# Upconversion.net
KiCad netlist of a schematic drawn in Altium Designer
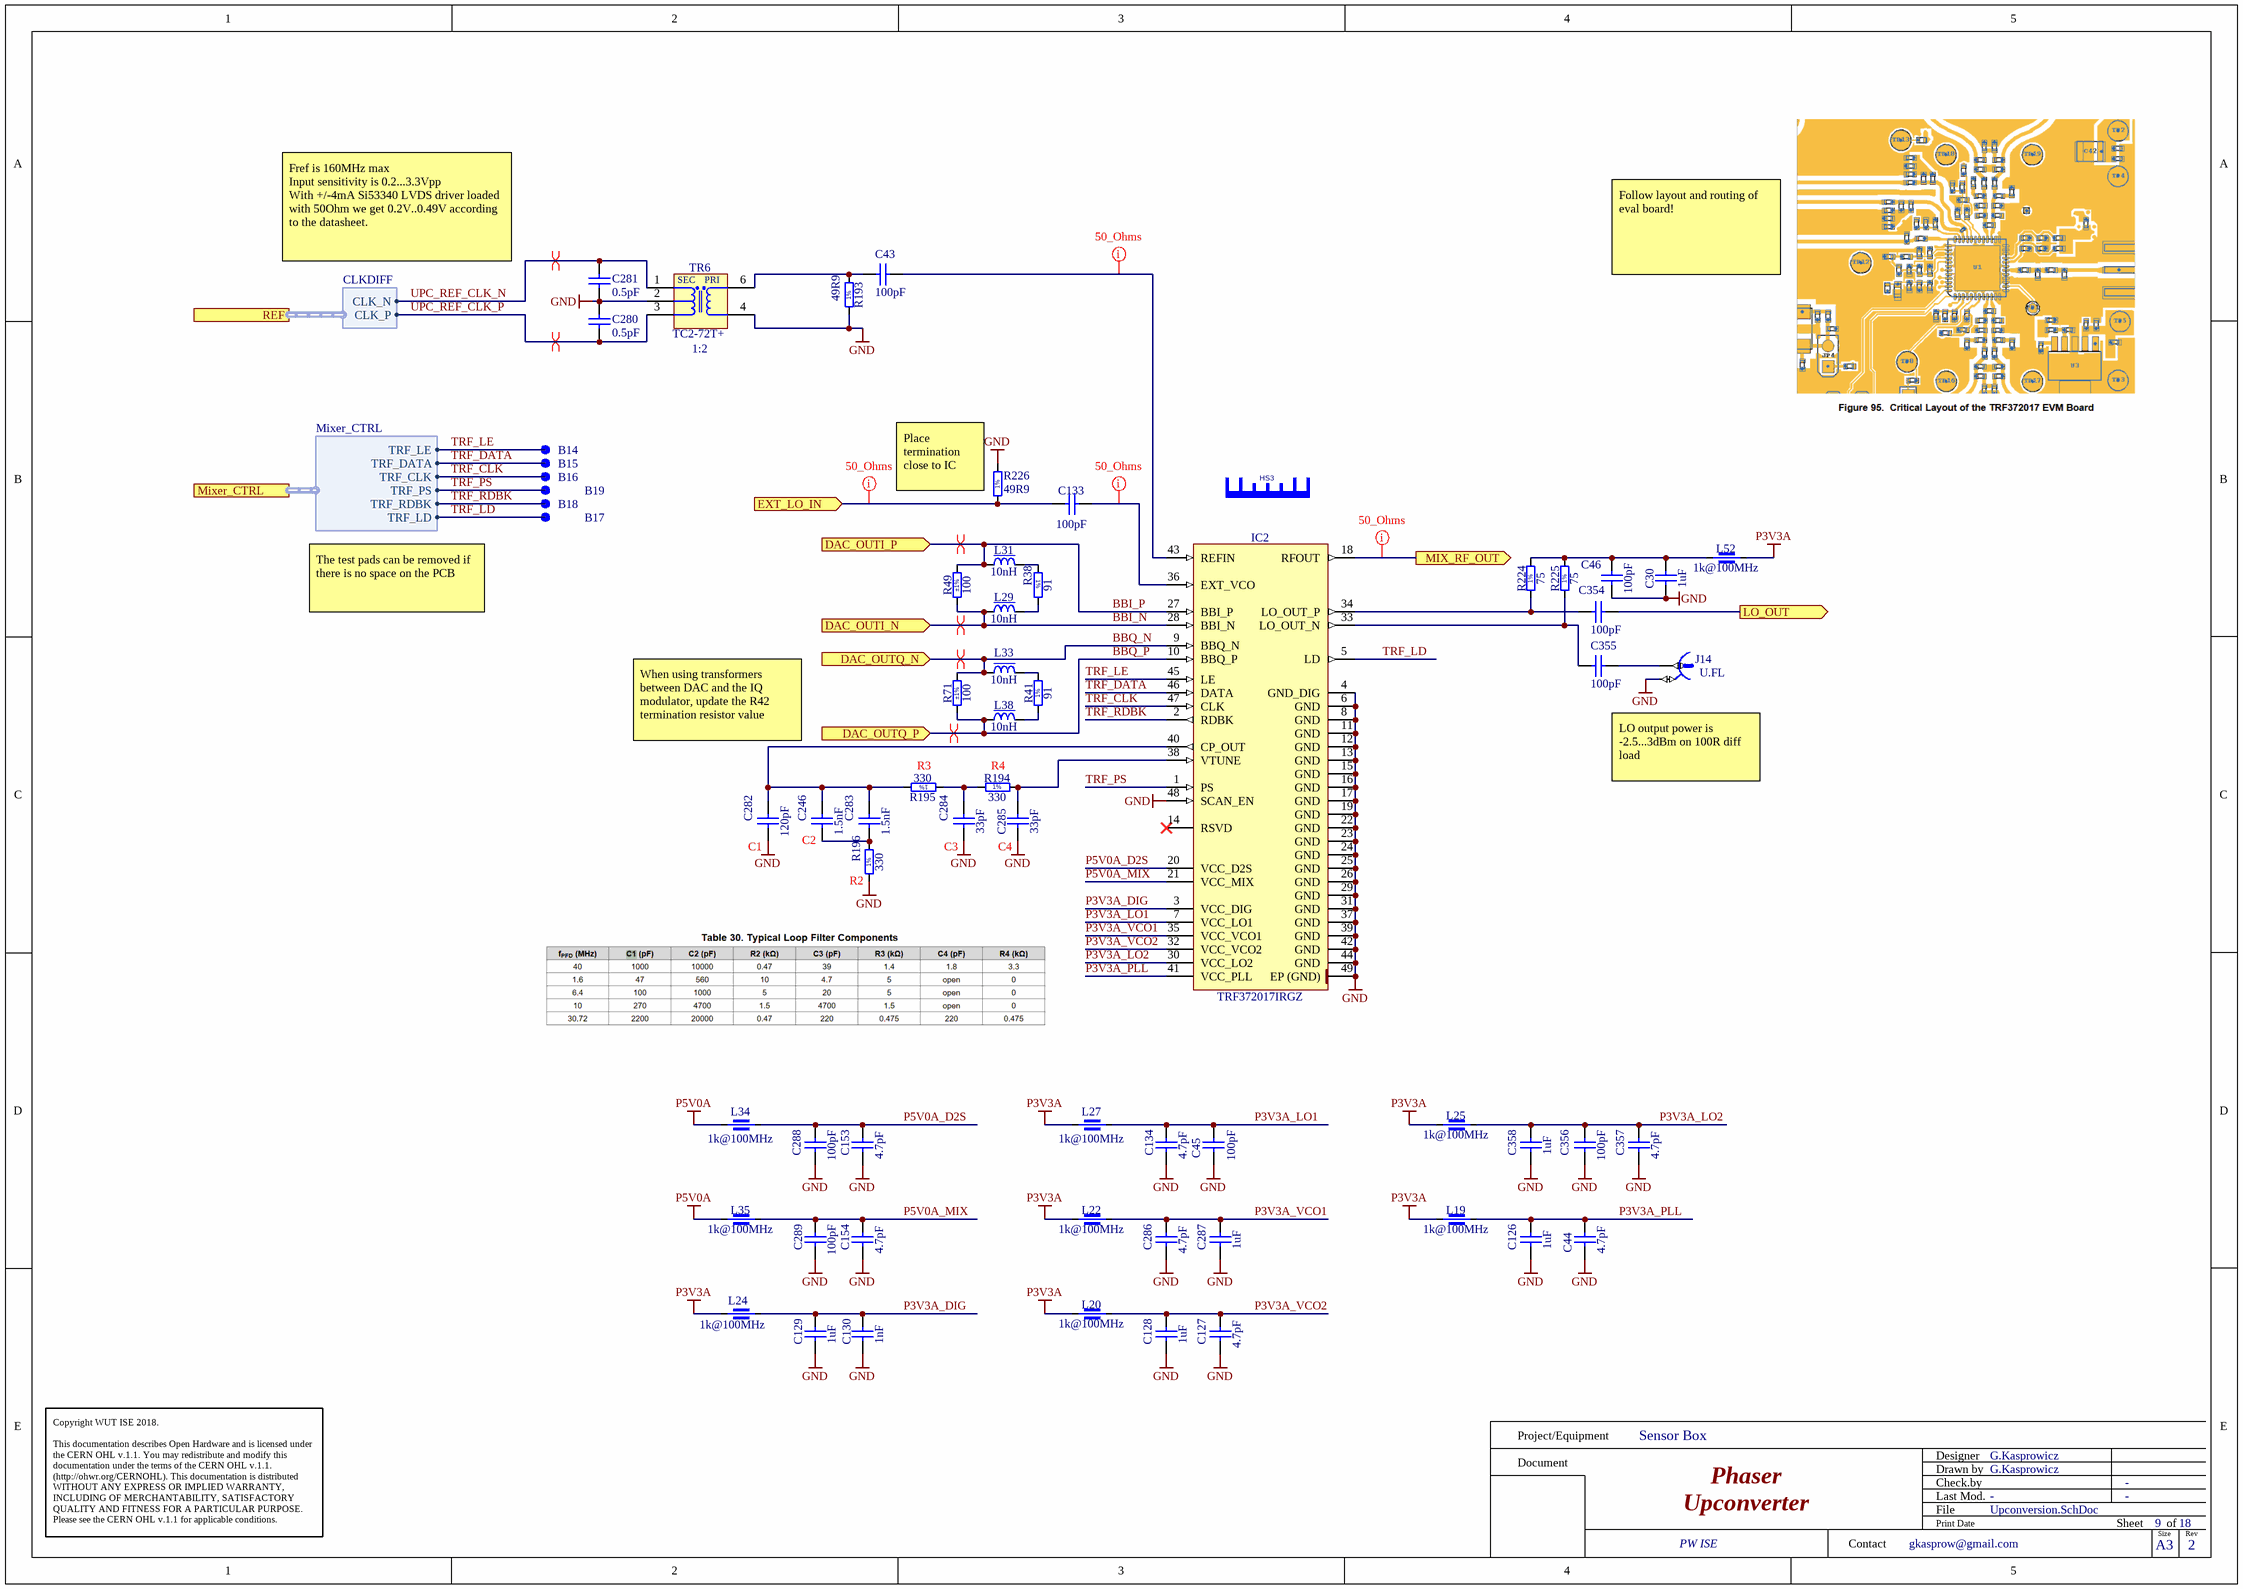
[diagram p0: Upconversion.SchDoc]

(export (version "E")
  (design (tool "Eeschema 10.0.6"))
  (components
    (comp (ref "B14")
      (value "SMD Pad")
      (footprint "C100")
      (description "Through Hole Pad")
      (fields (field (name "PART NUMBER") "SMD_PAD_D1MM") (field (name "AUTHOR") "CERN DEM JLC"))
      (libsource (lib "Eletro-mechanical") (part "Single SMD Pad (Round)"))
    )
    (comp (ref "B15")
      (value "SMD Pad")
      (footprint "C100")
      (description "Through Hole Pad")
      (fields (field (name "PART NUMBER") "SMD_PAD_D1MM") (field (name "AUTHOR") "CERN DEM JLC"))
      (libsource (lib "Eletro-mechanical") (part "Single SMD Pad (Round)"))
    )
    (comp (ref "B16")
      (value "SMD Pad")
      (footprint "C100")
      (description "Through Hole Pad")
      (fields (field (name "PART NUMBER") "SMD_PAD_D1MM") (field (name "AUTHOR") "CERN DEM JLC"))
      (libsource (lib "Eletro-mechanical") (part "Single SMD Pad (Round)"))
    )
    (comp (ref "B17")
      (value "SMD Pad")
      (footprint "C100")
      (description "Through Hole Pad")
      (fields (field (name "PART NUMBER") "SMD_PAD_D1MM") (field (name "AUTHOR") "CERN DEM JLC"))
      (libsource (lib "Eletro-mechanical") (part "Single SMD Pad (Round)"))
    )
    (comp (ref "B18")
      (value "SMD Pad")
      (footprint "C100")
      (description "Through Hole Pad")
      (fields (field (name "PART NUMBER") "SMD_PAD_D1MM") (field (name "AUTHOR") "CERN DEM JLC"))
      (libsource (lib "Eletro-mechanical") (part "Single SMD Pad (Round)"))
    )
    (comp (ref "B19")
      (value "SMD Pad")
      (footprint "C100")
      (description "Through Hole Pad")
      (fields (field (name "PART NUMBER") "SMD_PAD_D1MM") (field (name "AUTHOR") "CERN DEM JLC"))
      (libsource (lib "Eletro-mechanical") (part "Single SMD Pad (Round)"))
    )
    (comp (ref "C30")
      (value "1uF")
      (footprint "CAPC1005X55N")
      (description "Non-polarised capacitor")
      (fields
        (field (name "PART NUMBER") "CC0402_1UF_16V_10%_X5R")
        (field (name "VOLTAGE") "16V")
        (field (name "AUTHOR") "CERN DEM JLC")
      )
      (libsource (lib "Capacitors") (part "Capacitor - non polarized"))
    )
    (comp (ref "C43")
      (value "100pF")
      (footprint "CAPC1005X55N")
      (description "Non-polarised capacitor")
      (fields
        (field (name "PART NUMBER") "CC0402_100PF_50V_5%_C0G")
        (field (name "VOLTAGE") "50V")
        (field (name "AUTHOR") "CERN DEM JLC")
      )
      (libsource (lib "Capacitors") (part "Capacitor - non polarized"))
    )
    (comp (ref "C44")
      (value "4.7pF")
      (footprint "CAPC1005X55N")
      (description "Non-polarised capacitor")
      (fields
        (field (name "PART NUMBER") "CC0402_4.7PF_50V_0.25PF_C0G")
        (field (name "VOLTAGE") "50V")
        (field (name "AUTHOR") "CERN DEM JLC")
      )
      (libsource (lib "Capacitors") (part "Capacitor - non polarized"))
    )
    (comp (ref "C45")
      (value "100pF")
      (footprint "CAPC1005X55N")
      (description "Non-polarised capacitor")
      (fields
        (field (name "PART NUMBER") "CC0402_100PF_50V_5%_C0G")
        (field (name "VOLTAGE") "50V")
        (field (name "AUTHOR") "CERN DEM JLC")
      )
      (libsource (lib "Capacitors") (part "Capacitor - non polarized"))
    )
    (comp (ref "C46")
      (value "100pF")
      (footprint "CAPC1005X55N")
      (description "Non-polarised capacitor")
      (fields
        (field (name "PART NUMBER") "CC0402_100PF_50V_5%_C0G")
        (field (name "VOLTAGE") "50V")
        (field (name "AUTHOR") "CERN DEM JLC")
      )
      (libsource (lib "Capacitors") (part "Capacitor - non polarized"))
    )
    (comp (ref "C126")
      (value "1uF")
      (footprint "CAPC1005X55N")
      (description "Non-polarised capacitor")
      (fields
        (field (name "PART NUMBER") "CC0402_1UF_16V_10%_X5R")
        (field (name "VOLTAGE") "16V")
        (field (name "AUTHOR") "CERN DEM JLC")
      )
      (libsource (lib "Capacitors") (part "Capacitor - non polarized"))
    )
    (comp (ref "C127")
      (value "4.7pF")
      (footprint "CAPC1005X55N")
      (description "Non-polarised capacitor")
      (fields
        (field (name "PART NUMBER") "CC0402_4.7PF_50V_0.25PF_C0G")
        (field (name "VOLTAGE") "50V")
        (field (name "AUTHOR") "CERN DEM JLC")
      )
      (libsource (lib "Capacitors") (part "Capacitor - non polarized"))
    )
    (comp (ref "C128")
      (value "1uF")
      (footprint "CAPC1005X55N")
      (description "Non-polarised capacitor")
      (fields
        (field (name "PART NUMBER") "CC0402_1UF_16V_10%_X5R")
        (field (name "VOLTAGE") "16V")
        (field (name "AUTHOR") "CERN DEM JLC")
      )
      (libsource (lib "Capacitors") (part "Capacitor - non polarized"))
    )
    (comp (ref "C129")
      (value "1uF")
      (footprint "CAPC1005X55N")
      (description "Non-polarised capacitor")
      (fields
        (field (name "PART NUMBER") "CC0402_1UF_16V_10%_X5R")
        (field (name "VOLTAGE") "16V")
        (field (name "AUTHOR") "CERN DEM JLC")
      )
      (libsource (lib "Capacitors") (part "Capacitor - non polarized"))
    )
    (comp (ref "C130")
      (value "1nF")
      (footprint "CAPC1005X55N")
      (description "Non-polarised capacitor")
      (fields
        (field (name "PART NUMBER") "CC0402_1NF_50V_10%_X7R")
        (field (name "VOLTAGE") "50V")
        (field (name "AUTHOR") "CERN DEM JLC")
      )
      (libsource (lib "Capacitors") (part "Capacitor - non polarized"))
    )
    (comp (ref "C133")
      (value "100pF")
      (footprint "CAPC1005X55N")
      (description "Non-polarised capacitor")
      (fields
        (field (name "PART NUMBER") "CC0402_100PF_50V_5%_C0G")
        (field (name "VOLTAGE") "50V")
        (field (name "AUTHOR") "CERN DEM JLC")
      )
      (libsource (lib "Capacitors") (part "Capacitor - non polarized"))
    )
    (comp (ref "C134")
      (value "4.7pF")
      (footprint "CAPC1005X55N")
      (description "Non-polarised capacitor")
      (fields
        (field (name "PART NUMBER") "CC0402_4.7PF_50V_0.25PF_C0G")
        (field (name "VOLTAGE") "50V")
        (field (name "AUTHOR") "CERN DEM JLC")
      )
      (libsource (lib "Capacitors") (part "Capacitor - non polarized"))
    )
    (comp (ref "C153")
      (value "4.7pF")
      (footprint "CAPC1005X55N")
      (description "Non-polarised capacitor")
      (fields
        (field (name "PART NUMBER") "CC0402_4.7PF_50V_0.25PF_C0G")
        (field (name "VOLTAGE") "50V")
        (field (name "AUTHOR") "CERN DEM JLC")
      )
      (libsource (lib "Capacitors") (part "Capacitor - non polarized"))
    )
    (comp (ref "C154")
      (value "4.7pF")
      (footprint "CAPC1005X55N")
      (description "Non-polarised capacitor")
      (fields
        (field (name "PART NUMBER") "CC0402_4.7PF_50V_0.25PF_C0G")
        (field (name "VOLTAGE") "50V")
        (field (name "AUTHOR") "CERN DEM JLC")
      )
      (libsource (lib "Capacitors") (part "Capacitor - non polarized"))
    )
    (comp (ref "C246")
      (value "1.5nF")
      (footprint "CAPC1608X87N")
      (description "Non-polarised capacitor")
      (fields
        (field (name "PART NUMBER") "CC0603_1.5NF_50V_5%_NP0")
        (field (name "VOLTAGE") "50V")
        (field (name "AUTHOR") "CERN DEM JLC")
      )
      (libsource (lib "Capacitors") (part "Capacitor - non polarized"))
    )
    (comp (ref "C280")
      (value "0.5pF")
      (footprint "CAPC1005X50N")
      (description "Non-polarised capacitor")
      (fields
        (field (name "PART NUMBER") "CC0402_0.5PF_25V_0.05PF_AVX_04023J0R5ABSTR")
        (field (name "VOLTAGE") "25V")
        (field (name "AUTHOR") "CERN DEM JLC")
      )
      (libsource (lib "Capacitors") (part "Capacitor - non polarized"))
    )
    (comp (ref "C281")
      (value "0.5pF")
      (footprint "CAPC1005X50N")
      (description "Non-polarised capacitor")
      (fields
        (field (name "PART NUMBER") "CC0402_0.5PF_25V_0.05PF_AVX_04023J0R5ABSTR")
        (field (name "VOLTAGE") "25V")
        (field (name "AUTHOR") "CERN DEM JLC")
      )
      (libsource (lib "Capacitors") (part "Capacitor - non polarized"))
    )
    (comp (ref "C282")
      (value "120pF")
      (footprint "CAPC1608X87N")
      (description "Non-polarised capacitor")
      (fields
        (field (name "PART NUMBER") "CC0603_120PF_50V_5%_NP0")
        (field (name "VOLTAGE") "50V")
        (field (name "AUTHOR") "CERN DEM JLC")
      )
      (libsource (lib "Capacitors") (part "Capacitor - non polarized"))
    )
    (comp (ref "C283")
      (value "1.5nF")
      (footprint "CAPC1608X87N")
      (description "Non-polarised capacitor")
      (fields
        (field (name "PART NUMBER") "CC0603_1.5NF_50V_5%_NP0")
        (field (name "VOLTAGE") "50V")
        (field (name "AUTHOR") "CERN DEM JLC")
      )
      (libsource (lib "Capacitors") (part "Capacitor - non polarized"))
    )
    (comp (ref "C284")
      (value "33pF")
      (footprint "CAPC2012X135N")
      (description "Non-polarised capacitor")
      (fields
        (field (name "PART NUMBER") "CC0805_33PF_50V_5%_NP0")
        (field (name "VOLTAGE") "50V")
        (field (name "AUTHOR") "CERN DEM JLC")
      )
      (libsource (lib "Capacitors") (part "Capacitor - non polarized"))
    )
    (comp (ref "C285")
      (value "33pF")
      (footprint "CAPC2012X135N")
      (description "Non-polarised capacitor")
      (fields
        (field (name "PART NUMBER") "CC0805_33PF_50V_5%_NP0")
        (field (name "MANUFACTURER") "GENERIC")
        (field (name "AUTHOR") "CERN DEM JLC")
      )
      (libsource (lib "Capacitors") (part "Capacitor - non polarized"))
    )
    (comp (ref "C286")
      (value "4.7pF")
      (footprint "CAPC1005X55N")
      (description "Non-polarised capacitor")
      (fields
        (field (name "PART NUMBER") "CC0402_4.7PF_50V_0.25PF_C0G")
        (field (name "VOLTAGE") "50V")
        (field (name "AUTHOR") "CERN DEM JLC")
      )
      (libsource (lib "Capacitors") (part "Capacitor - non polarized"))
    )
    (comp (ref "C287")
      (value "1uF")
      (footprint "CAPC1005X55N")
      (description "Non-polarised capacitor")
      (fields
        (field (name "PART NUMBER") "CC0402_1UF_16V_10%_X5R")
        (field (name "VOLTAGE") "16V")
        (field (name "AUTHOR") "CERN DEM JLC")
      )
      (libsource (lib "Capacitors") (part "Capacitor - non polarized"))
    )
    (comp (ref "C288")
      (value "100pF")
      (footprint "CAPC1005X55N")
      (description "Non-polarised capacitor")
      (fields
        (field (name "PART NUMBER") "CC0402_100PF_50V_5%_C0G")
        (field (name "VOLTAGE") "50V")
        (field (name "AUTHOR") "CERN DEM JLC")
      )
      (libsource (lib "Capacitors") (part "Capacitor - non polarized"))
    )
    (comp (ref "C289")
      (value "100pF")
      (footprint "CAPC1005X55N")
      (description "Non-polarised capacitor")
      (fields
        (field (name "PART NUMBER") "CC0402_100PF_50V_5%_C0G")
        (field (name "VOLTAGE") "50V")
        (field (name "AUTHOR") "CERN DEM JLC")
      )
      (libsource (lib "Capacitors") (part "Capacitor - non polarized"))
    )
    (comp (ref "C354")
      (value "100pF")
      (footprint "CAPC1005X55N")
      (description "Non-polarised capacitor")
      (fields
        (field (name "PART NUMBER") "CC0402_100PF_50V_5%_C0G")
        (field (name "VOLTAGE") "50V")
        (field (name "AUTHOR") "CERN DEM JLC")
      )
      (libsource (lib "Capacitors") (part "Capacitor - non polarized"))
    )
    (comp (ref "C355")
      (value "100pF")
      (footprint "CAPC1005X55N")
      (description "Non-polarised capacitor")
      (fields
        (field (name "PART NUMBER") "CC0402_100PF_50V_5%_C0G")
        (field (name "VOLTAGE") "50V")
        (field (name "AUTHOR") "CERN DEM JLC")
      )
      (libsource (lib "Capacitors") (part "Capacitor - non polarized"))
    )
    (comp (ref "C356")
      (value "100pF")
      (footprint "CAPC1005X55N")
      (description "Non-polarised capacitor")
      (fields
        (field (name "PART NUMBER") "CC0402_100PF_50V_5%_C0G")
        (field (name "VOLTAGE") "50V")
        (field (name "AUTHOR") "CERN DEM JLC")
      )
      (libsource (lib "Capacitors") (part "Capacitor - non polarized"))
    )
    (comp (ref "C357")
      (value "4.7pF")
      (footprint "CAPC1005X55N")
      (description "Non-polarised capacitor")
      (fields
        (field (name "PART NUMBER") "CC0402_4.7PF_50V_0.25PF_C0G")
        (field (name "VOLTAGE") "50V")
        (field (name "AUTHOR") "CERN DEM JLC")
      )
      (libsource (lib "Capacitors") (part "Capacitor - non polarized"))
    )
    (comp (ref "C358")
      (value "1uF")
      (footprint "CAPC1005X55N")
      (description "Non-polarised capacitor")
      (fields
        (field (name "PART NUMBER") "CC0402_1UF_16V_10%_X5R")
        (field (name "VOLTAGE") "16V")
        (field (name "AUTHOR") "CERN DEM JLC")
      )
      (libsource (lib "Capacitors") (part "Capacitor - non polarized"))
    )
    (comp (ref "HS3")
      (value "Heat Sink No Pad")
      (footprint "HSINK_17156")
      (description "Alphacool GPU RAM Aluminium Heatsinks 7x7mm - black")
      (fields
        (field (name "PART NUMBER") "4250197171564")
        (field (name "MANUFACTURER") "Alphacool")
        (field (name "AUTHOR") "GK")
      )
      (libsource (lib "Mechanical") (part "HEAT_SINK_IC_7x7x15"))
    )
    (comp (ref "IC2")
      (value "TRF372017IRGZ")
      (footprint "QFN50P700X700X100-49N-S560")
      (description "Integrated IQ Modulator PLL/VCO")
      (fields (field (name "MANUFACTURER") "TEXAS INSTRUMENTS") (field (name "AUTHOR") "CERN DEM JMW"))
      (libsource (lib "ICs And Semiconductors") (part "TRF372017"))
    )
    (comp (ref "J14")
      (value "U.FL")
      (footprint "HIROSE_U.FL-R-SMT-1(10)")
      (fields
        (field (name "MANUFACTURER") "HIROSE (HRS)")
        (field (name "MANUFACTURER PART NUMBER") "U.FL-R-SMT-1(10)")
        (field (name "PART NUMBER") "HIROSE_U.FL-R-SMT-1(10)")
        (field (name "AUTHOR") "CERN DEM JLC")
      )
      (libsource (lib "Connectors") (part "Coax_1Male_1Shield"))
    )
    (comp (ref "L19")
      (value "1k@100MHz")
      (footprint "INDC1005X55N")
      (fields
        (field (name "PART NUMBER") "IND0402_MURATA_BLM15HD102SN1")
        (field (name "POWER") "250mA")
        (field (name "TOLERANCE") "±25%")
        (field (name "AUTHOR") "CERN DEM JLC")
      )
      (libsource (lib "Inductors & Transformers") (part "Ferrite Bead"))
    )
    (comp (ref "L20")
      (value "1k@100MHz")
      (footprint "INDC1005X55N")
      (fields
        (field (name "PART NUMBER") "IND0402_MURATA_BLM15HD102SN1")
        (field (name "POWER") "250mA")
        (field (name "TOLERANCE") "±25%")
        (field (name "AUTHOR") "CERN DEM JLC")
      )
      (libsource (lib "Inductors & Transformers") (part "Ferrite Bead"))
    )
    (comp (ref "L22")
      (value "1k@100MHz")
      (footprint "INDC1005X55N")
      (fields
        (field (name "PART NUMBER") "IND0402_MURATA_BLM15HD102SN1")
        (field (name "POWER") "250mA")
        (field (name "TOLERANCE") "±25%")
        (field (name "AUTHOR") "CERN DEM JLC")
      )
      (libsource (lib "Inductors & Transformers") (part "Ferrite Bead"))
    )
    (comp (ref "L24")
      (value "1k@100MHz")
      (footprint "INDC1005X55N")
      (fields
        (field (name "PART NUMBER") "IND0402_MURATA_BLM15HD102SN1")
        (field (name "POWER") "250mA")
        (field (name "TOLERANCE") "±25%")
        (field (name "AUTHOR") "CERN DEM JLC")
      )
      (libsource (lib "") (part "Ferrite Bead_1"))
    )
    (comp (ref "L25")
      (value "1k@100MHz")
      (footprint "INDC1005X55N")
      (fields
        (field (name "PART NUMBER") "IND0402_MURATA_BLM15HD102SN1")
        (field (name "POWER") "250mA")
        (field (name "TOLERANCE") "±25%")
        (field (name "AUTHOR") "CERN DEM JLC")
      )
      (libsource (lib "Inductors & Transformers") (part "Ferrite Bead"))
    )
    (comp (ref "L27")
      (value "1k@100MHz")
      (footprint "INDC1005X55N")
      (fields
        (field (name "PART NUMBER") "IND0402_MURATA_BLM15HD102SN1")
        (field (name "POWER") "250mA")
        (field (name "TOLERANCE") "±25%")
        (field (name "AUTHOR") "CERN DEM JLC")
      )
      (libsource (lib "") (part "Ferrite Bead_2"))
    )
    (comp (ref "L29")
      (value "10nH")
      (footprint "IND_COILCRAFT_0402DC")
      (description "Inductor With Core")
      (fields
        (field (name "PART NUMBER") "IND0402_10NH_2%_COILCRAFT_0402DC")
        (field (name "POWER") "1A")
        (field (name "AUTHOR") "GK")
      )
      (libsource (lib "Inductors_Transformers") (part "IND0402_10NH_2%_COILCRAFT_0402DC"))
    )
    (comp (ref "L31")
      (value "10nH")
      (footprint "IND_COILCRAFT_0402DC")
      (description "Inductor With Core")
      (fields
        (field (name "PART NUMBER") "IND0402_10NH_2%_COILCRAFT_0402DC")
        (field (name "POWER") "1A")
        (field (name "AUTHOR") "GK")
      )
      (libsource (lib "Inductors_Transformers") (part "IND0402_10NH_2%_COILCRAFT_0402DC"))
    )
    (comp (ref "L33")
      (value "10nH")
      (footprint "IND_COILCRAFT_0402DC")
      (description "Inductor With Core")
      (fields
        (field (name "PART NUMBER") "IND0402_10NH_2%_COILCRAFT_0402DC")
        (field (name "POWER") "1A")
        (field (name "AUTHOR") "GK")
      )
      (libsource (lib "Inductors_Transformers") (part "IND0402_10NH_2%_COILCRAFT_0402DC"))
    )
    (comp (ref "L34")
      (value "1k@100MHz")
      (footprint "INDC1005X55N")
      (fields
        (field (name "PART NUMBER") "IND0402_MURATA_BLM15HD102SN1")
        (field (name "POWER") "250mA")
        (field (name "TOLERANCE") "±25%")
        (field (name "AUTHOR") "CERN DEM JLC")
      )
      (libsource (lib "") (part "Ferrite Bead_2"))
    )
    (comp (ref "L35")
      (value "1k@100MHz")
      (footprint "INDC1005X55N")
      (fields
        (field (name "PART NUMBER") "IND0402_MURATA_BLM15HD102SN1")
        (field (name "POWER") "250mA")
        (field (name "TOLERANCE") "±25%")
        (field (name "AUTHOR") "CERN DEM JLC")
      )
      (libsource (lib "Inductors & Transformers") (part "Ferrite Bead"))
    )
    (comp (ref "L38")
      (value "10nH")
      (footprint "IND_COILCRAFT_0402DC")
      (description "Inductor With Core")
      (fields
        (field (name "PART NUMBER") "IND0402_10NH_2%_COILCRAFT_0402DC")
        (field (name "POWER") "1A")
        (field (name "AUTHOR") "GK")
      )
      (libsource (lib "Inductors_Transformers") (part "IND0402_10NH_2%_COILCRAFT_0402DC"))
    )
    (comp (ref "L52")
      (value "1k@100MHz")
      (footprint "INDC1005X55N")
      (fields
        (field (name "PART NUMBER") "IND0402_MURATA_BLM15HD102SN1")
        (field (name "POWER") "250mA")
        (field (name "TOLERANCE") "±25%")
        (field (name "AUTHOR") "CERN DEM JLC")
      )
      (libsource (lib "") (part "Ferrite Bead_2"))
    )
    (comp (ref "R38")
      (value "91")
      (footprint "RESC1005X40N")
      (description "Resistor - 1%")
      (fields
        (field (name "PART NUMBER") "R0402_91R_1%_0.0625W_100PPM")
        (field (name "POWER") "0.0625W")
        (field (name "AUTHOR") "CERN DEM JLC")
      )
      (libsource (lib "Resistors") (part "Resistor - 1%"))
    )
    (comp (ref "R41")
      (value "91")
      (footprint "RESC1005X40N")
      (description "Resistor - 1%")
      (fields
        (field (name "PART NUMBER") "R0402_91R_1%_0.0625W_100PPM")
        (field (name "POWER") "0.0625W")
        (field (name "AUTHOR") "CERN DEM JLC")
      )
      (libsource (lib "Resistors") (part "Resistor - 1%"))
    )
    (comp (ref "R49")
      (value "100")
      (footprint "RESC1005X40N")
      (description "Resistor - 1%")
      (fields
        (field (name "TOLERANCE") "±1%")
        (field (name "PART NUMBER") "R0402_100R_1%_0.0625W_100PPM")
        (field (name "POWER") "0.0625W")
        (field (name "AUTHOR") "CERN DEM JLC")
      )
      (libsource (lib "") (part "Resistor - 1%_1"))
    )
    (comp (ref "R71")
      (value "100")
      (footprint "RESC1005X40N")
      (description "Resistor - 1%")
      (fields
        (field (name "TOLERANCE") "±1%")
        (field (name "PART NUMBER") "R0402_100R_1%_0.0625W_100PPM")
        (field (name "POWER") "0.0625W")
        (field (name "AUTHOR") "CERN DEM JLC")
      )
      (libsource (lib "") (part "Resistor - 1%_1"))
    )
    (comp (ref "R193")
      (value "49R9")
      (footprint "RESC1005X40N")
      (description "Resistor - 1%")
      (fields
        (field (name "PART NUMBER") "R0402_49R9_1%_0.0625W_100PPM")
        (field (name "POWER") "0.0625W")
        (field (name "AUTHOR") "CERN DEM JLC")
      )
      (libsource (lib "Resistors") (part "Resistor - 1%"))
    )
    (comp (ref "R194")
      (value "330")
      (footprint "RESC1608X55N")
      (description "Resistor - 1%")
      (fields
        (field (name "PART NUMBER") "R0603_330R_1%_0.1W_100PPM")
        (field (name "MANUFACTURER") "GENERIC")
        (field (name "AUTHOR") "CERN DEM JLC")
      )
      (libsource (lib "Resistors") (part "Resistor - 1%"))
    )
    (comp (ref "R195")
      (value "330")
      (footprint "RESC1608X55N")
      (description "Resistor - 1%")
      (fields
        (field (name "PART NUMBER") "R0603_330R_1%_0.1W_100PPM")
        (field (name "POWER") "0.1W")
        (field (name "AUTHOR") "CERN DEM JLC")
      )
      (libsource (lib "Resistors") (part "Resistor - 1%"))
    )
    (comp (ref "R196")
      (value "330")
      (footprint "RESC1608X55N")
      (description "Resistor - 1%")
      (fields
        (field (name "PART NUMBER") "R0603_330R_1%_0.1W_100PPM")
        (field (name "POWER") "0.1W")
        (field (name "AUTHOR") "CERN DEM JLC")
      )
      (libsource (lib "Resistors") (part "Resistor - 1%"))
    )
    (comp (ref "R224")
      (value "75")
      (footprint "RESC1005X40N")
      (description "Resistor - 1%")
      (fields
        (field (name "PART NUMBER") "R0402_75R_1%_0.0625W_100PPM")
        (field (name "POWER") "0.0625W")
        (field (name "AUTHOR") "CERN DEM JLC")
      )
      (libsource (lib "Resistors") (part "Resistor - 1%"))
    )
    (comp (ref "R225")
      (value "75")
      (footprint "RESC1005X40N")
      (description "Resistor - 1%")
      (fields
        (field (name "PART NUMBER") "R0402_75R_1%_0.0625W_100PPM")
        (field (name "POWER") "0.0625W")
        (field (name "AUTHOR") "CERN DEM JLC")
      )
      (libsource (lib "Resistors") (part "Resistor - 1%"))
    )
    (comp (ref "R226")
      (value "49R9")
      (footprint "RESC1005X40N")
      (description "Resistor - 1%")
      (fields
        (field (name "PART NUMBER") "R0402_49R9_1%_0.0625W_100PPM")
        (field (name "POWER") "0.0625W")
        (field (name "AUTHOR") "CERN DEM JLC")
      )
      (libsource (lib "Resistors") (part "Resistor - 1%"))
    )
    (comp (ref "TR6")
      (value "1:2")
      (footprint "XFMR_MINI-CIRCUITS_AT1521")
      (description "50 Ohms 10 to 700 MHzz RF Transformer")
      (fields
        (field (name "MANUFACTURER") "MINI-CIRCUITS")
        (field (name "MANUFACTURER PART NUMBER") "TC2-72T+")
        (field (name "PART NUMBER") "XFMR_MINI-CIRCUITS_TC2-72T+")
        (field (name "AUTHOR") "GK")
      )
      (libsource (lib "Inductors_Transformers") (part "XFMR_MINI-CIRCUITS_TC2-72T+"))
    )
  )
  (nets
    (net (code "3") (name "/BBI_N") (class "Default")
      (node (ref "IC2") (pin "28") (pinfunction "BBI_N_28") (pintype "input"))
      (node (ref "L29") (pin "1") (pinfunction "1_1") (pintype "passive"))
      (node (ref "R49") (pin "1") (pinfunction "1_1") (pintype "passive"))
    )
    (net (code "4") (name "/BBI_P") (class "Default")
      (node (ref "IC2") (pin "27") (pinfunction "BBI_P_27") (pintype "input"))
      (node (ref "L31") (pin "1") (pinfunction "1_1") (pintype "passive"))
      (node (ref "R49") (pin "2") (pinfunction "2_2") (pintype "passive"))
    )
    (net (code "5") (name "/BBQ_N") (class "Default")
      (node (ref "IC2") (pin "9") (pinfunction "BBQ_N_9") (pintype "input"))
      (node (ref "L33") (pin "1") (pinfunction "1_1") (pintype "passive"))
      (node (ref "R71") (pin "2") (pinfunction "2_2") (pintype "passive"))
    )
    (net (code "6") (name "/BBQ_P") (class "Default")
      (node (ref "IC2") (pin "10") (pinfunction "BBQ_P_10") (pintype "input"))
      (node (ref "L38") (pin "1") (pinfunction "1_1") (pintype "passive"))
      (node (ref "R71") (pin "1") (pinfunction "1_1") (pintype "passive"))
    )
    (net (code "7") (name "/EXT_LO_IN") (class "Default")
      (node (ref "C133") (pin "1") (pinfunction "1_1") (pintype "passive"))
      (node (ref "R226") (pin "1") (pinfunction "1_1") (pintype "passive"))
    )
    (net (code "8") (name "/LO_OUT") (class "Default")
      (node (ref "C354") (pin "1") (pinfunction "1_1") (pintype "passive"))
    )
    (net (code "9") (name "/MIX_RF_OUT") (class "Default")
      (node (ref "IC2") (pin "18") (pinfunction "RFOUT_18") (pintype "output"))
    )
    (net (code "10") (name "/P3V3A_DIG") (class "Default")
      (node (ref "C129") (pin "2") (pinfunction "2_2") (pintype "passive"))
      (node (ref "C130") (pin "2") (pinfunction "2_2") (pintype "passive"))
      (node (ref "IC2") (pin "3") (pinfunction "VCC_DIG_3") (pintype "power_in"))
      (node (ref "L24") (pin "1") (pinfunction "1_1") (pintype "passive"))
    )
    (net (code "11") (name "/P3V3A_LO1") (class "Default")
      (node (ref "C134") (pin "2") (pinfunction "2_2") (pintype "passive"))
      (node (ref "C45") (pin "2") (pinfunction "2_2") (pintype "passive"))
      (node (ref "IC2") (pin "7") (pinfunction "VCC_LO1_7") (pintype "power_in"))
      (node (ref "L27") (pin "2") (pinfunction "2_2") (pintype "passive"))
    )
    (net (code "12") (name "/P3V3A_LO2") (class "Default")
      (node (ref "C356") (pin "2") (pinfunction "2_2") (pintype "passive"))
      (node (ref "C357") (pin "2") (pinfunction "2_2") (pintype "passive"))
      (node (ref "C358") (pin "2") (pinfunction "2_2") (pintype "passive"))
      (node (ref "IC2") (pin "30") (pinfunction "VCC_LO2_30") (pintype "power_in"))
      (node (ref "L25") (pin "1") (pinfunction "1_1") (pintype "passive"))
    )
    (net (code "13") (name "/P3V3A_PLL") (class "Default")
      (node (ref "C126") (pin "2") (pinfunction "2_2") (pintype "passive"))
      (node (ref "C44") (pin "2") (pinfunction "2_2") (pintype "passive"))
      (node (ref "IC2") (pin "41") (pinfunction "VCC_PLL_41") (pintype "power_in"))
      (node (ref "L19") (pin "1") (pinfunction "1_1") (pintype "passive"))
    )
    (net (code "14") (name "/P3V3A_VCO1") (class "Default")
      (node (ref "C286") (pin "2") (pinfunction "2_2") (pintype "passive"))
      (node (ref "C287") (pin "2") (pinfunction "2_2") (pintype "passive"))
      (node (ref "IC2") (pin "35") (pinfunction "VCC_VCO1_35") (pintype "power_in"))
      (node (ref "L22") (pin "1") (pinfunction "1_1") (pintype "passive"))
    )
    (net (code "15") (name "/P3V3A_VCO2") (class "Default")
      (node (ref "C127") (pin "2") (pinfunction "2_2") (pintype "passive"))
      (node (ref "C128") (pin "2") (pinfunction "2_2") (pintype "passive"))
      (node (ref "IC2") (pin "32") (pinfunction "VCC_VCO2_32") (pintype "power_in"))
      (node (ref "L20") (pin "1") (pinfunction "1_1") (pintype "passive"))
    )
    (net (code "16") (name "/P5V0A_D2S") (class "Default")
      (node (ref "C153") (pin "2") (pinfunction "2_2") (pintype "passive"))
      (node (ref "C288") (pin "2") (pinfunction "2_2") (pintype "passive"))
      (node (ref "IC2") (pin "20") (pinfunction "VCC_D2S_20") (pintype "power_in"))
      (node (ref "L34") (pin "2") (pinfunction "2_2") (pintype "passive"))
    )
    (net (code "17") (name "/P5V0A_MIX") (class "Default")
      (node (ref "C154") (pin "2") (pinfunction "2_2") (pintype "passive"))
      (node (ref "C289") (pin "2") (pinfunction "2_2") (pintype "passive"))
      (node (ref "IC2") (pin "21") (pinfunction "VCC_MIX_21") (pintype "power_in"))
      (node (ref "L35") (pin "1") (pinfunction "1_1") (pintype "passive"))
    )
    (net (code "18") (name "/TRF_CLK") (class "Default")
      (node (ref "B16") (pin "1") (pinfunction "1_1") (pintype "bidirectional"))
      (node (ref "IC2") (pin "47") (pinfunction "CLK_47") (pintype "input"))
    )
    (net (code "19") (name "/TRF_DATA") (class "Default")
      (node (ref "B15") (pin "1") (pinfunction "1_1") (pintype "bidirectional"))
      (node (ref "IC2") (pin "46") (pinfunction "DATA_46") (pintype "input"))
    )
    (net (code "20") (name "/TRF_LD") (class "Default")
      (node (ref "B17") (pin "1") (pinfunction "1_1") (pintype "bidirectional"))
      (node (ref "IC2") (pin "5") (pinfunction "LD_5") (pintype "output"))
    )
    (net (code "21") (name "/TRF_LE") (class "Default")
      (node (ref "B14") (pin "1") (pinfunction "1_1") (pintype "bidirectional"))
      (node (ref "IC2") (pin "45") (pinfunction "LE_45") (pintype "input"))
    )
    (net (code "22") (name "/TRF_PS") (class "Default")
      (node (ref "B19") (pin "1") (pinfunction "1_1") (pintype "bidirectional"))
      (node (ref "IC2") (pin "1") (pinfunction "PS_1") (pintype "input"))
    )
    (net (code "23") (name "/TRF_RDBK") (class "Default")
      (node (ref "B18") (pin "1") (pinfunction "1_1") (pintype "bidirectional"))
      (node (ref "IC2") (pin "2") (pinfunction "RDBK_2") (pintype "output"))
    )
    (net (code "24") (name "/UPC_REF_CLK_N") (class "Default")
      (node (ref "C281") (pin "1") (pinfunction "1_1") (pintype "passive"))
      (node (ref "TR6") (pin "1") (pinfunction "SDOT_1") (pintype "passive"))
    )
    (net (code "25") (name "/UPC_REF_CLK_P") (class "Default")
      (node (ref "C280") (pin "2") (pinfunction "2_2") (pintype "passive"))
      (node (ref "TR6") (pin "3") (pinfunction "S_3") (pintype "passive"))
    )
    (net (code "28") (name "GND") (class "Default")
      (node (ref "C126") (pin "1") (pinfunction "1_1") (pintype "passive"))
      (node (ref "C127") (pin "1") (pinfunction "1_1") (pintype "passive"))
      (node (ref "C128") (pin "1") (pinfunction "1_1") (pintype "passive"))
      (node (ref "C129") (pin "1") (pinfunction "1_1") (pintype "passive"))
      (node (ref "C130") (pin "1") (pinfunction "1_1") (pintype "passive"))
      (node (ref "C134") (pin "1") (pinfunction "1_1") (pintype "passive"))
      (node (ref "C153") (pin "1") (pinfunction "1_1") (pintype "passive"))
      (node (ref "C154") (pin "1") (pinfunction "1_1") (pintype "passive"))
      (node (ref "C280") (pin "1") (pinfunction "1_1") (pintype "passive"))
      (node (ref "C281") (pin "2") (pinfunction "2_2") (pintype "passive"))
      (node (ref "C282") (pin "1") (pinfunction "1_1") (pintype "passive"))
      (node (ref "C284") (pin "1") (pinfunction "1_1") (pintype "passive"))
      (node (ref "C285") (pin "1") (pinfunction "1_1") (pintype "passive"))
      (node (ref "C286") (pin "1") (pinfunction "1_1") (pintype "passive"))
      (node (ref "C287") (pin "1") (pinfunction "1_1") (pintype "passive"))
      (node (ref "C288") (pin "1") (pinfunction "1_1") (pintype "passive"))
      (node (ref "C289") (pin "1") (pinfunction "1_1") (pintype "passive"))
      (node (ref "C30") (pin "1") (pinfunction "1_1") (pintype "passive"))
      (node (ref "C356") (pin "1") (pinfunction "1_1") (pintype "passive"))
      (node (ref "C357") (pin "1") (pinfunction "1_1") (pintype "passive"))
      (node (ref "C358") (pin "1") (pinfunction "1_1") (pintype "passive"))
      (node (ref "C44") (pin "1") (pinfunction "1_1") (pintype "passive"))
      (node (ref "C45") (pin "1") (pinfunction "1_1") (pintype "passive"))
      (node (ref "C46") (pin "1") (pinfunction "1_1") (pintype "passive"))
      (node (ref "IC2") (pin "11") (pinfunction "GND_11") (pintype "power_in"))
      (node (ref "IC2") (pin "12") (pinfunction "GND_12") (pintype "power_in"))
      (node (ref "IC2") (pin "13") (pinfunction "GND_13") (pintype "power_in"))
      (node (ref "IC2") (pin "15") (pinfunction "GND_15") (pintype "power_in"))
      (node (ref "IC2") (pin "16") (pinfunction "GND_16") (pintype "power_in"))
      (node (ref "IC2") (pin "17") (pinfunction "GND_17") (pintype "power_in"))
      (node (ref "IC2") (pin "19") (pinfunction "GND_19") (pintype "power_in"))
      (node (ref "IC2") (pin "22") (pinfunction "GND_22") (pintype "power_in"))
      (node (ref "IC2") (pin "23") (pinfunction "GND_23") (pintype "power_in"))
      (node (ref "IC2") (pin "24") (pinfunction "GND_24") (pintype "power_in"))
      (node (ref "IC2") (pin "25") (pinfunction "GND_25") (pintype "power_in"))
      (node (ref "IC2") (pin "26") (pinfunction "GND_26") (pintype "power_in"))
      (node (ref "IC2") (pin "29") (pinfunction "GND_29") (pintype "power_in"))
      (node (ref "IC2") (pin "31") (pinfunction "GND_31") (pintype "power_in"))
      (node (ref "IC2") (pin "37") (pinfunction "GND_37") (pintype "power_in"))
      (node (ref "IC2") (pin "39") (pinfunction "GND_39") (pintype "power_in"))
      (node (ref "IC2") (pin "4") (pinfunction "GND_DIG_4") (pintype "power_in"))
      (node (ref "IC2") (pin "42") (pinfunction "GND_42") (pintype "power_in"))
      (node (ref "IC2") (pin "44") (pinfunction "GND_44") (pintype "power_in"))
      (node (ref "IC2") (pin "48") (pinfunction "SCAN_EN_48") (pintype "input"))
      (node (ref "IC2") (pin "49") (pinfunction "EP_(GND)_49") (pintype "power_in"))
      (node (ref "IC2") (pin "6") (pinfunction "GND_6") (pintype "power_in"))
      (node (ref "IC2") (pin "8") (pinfunction "GND_8") (pintype "power_in"))
      (node (ref "J14") (pin "2") (pinfunction "2_2") (pintype "bidirectional"))
      (node (ref "R193") (pin "1") (pinfunction "1_1") (pintype "passive"))
      (node (ref "R196") (pin "1") (pinfunction "1_1") (pintype "passive"))
      (node (ref "R226") (pin "2") (pinfunction "2_2") (pintype "passive"))
      (node (ref "TR6") (pin "2") (pinfunction "NC_2") (pintype "passive"))
      (node (ref "TR6") (pin "4") (pinfunction "P_4") (pintype "passive"))
    )
    (net (code "29") (name "Net-(C30-Pad2)") (class "Default")
      (node (ref "C30") (pin "2") (pinfunction "2_2") (pintype "passive"))
      (node (ref "C46") (pin "2") (pinfunction "2_2") (pintype "passive"))
      (node (ref "L52") (pin "1") (pinfunction "1_1") (pintype "passive"))
      (node (ref "R224") (pin "2") (pinfunction "2_2") (pintype "passive"))
      (node (ref "R225") (pin "2") (pinfunction "2_2") (pintype "passive"))
    )
    (net (code "30") (name "Net-(C246-Pad1)") (class "Default")
      (node (ref "C246") (pin "1") (pinfunction "1_1") (pintype "passive"))
      (node (ref "C283") (pin "1") (pinfunction "1_1") (pintype "passive"))
      (node (ref "R196") (pin "2") (pinfunction "2_2") (pintype "passive"))
    )
    (net (code "31") (name "Net-(C284-Pad2)") (class "Default")
      (node (ref "C284") (pin "2") (pinfunction "2_2") (pintype "passive"))
      (node (ref "R194") (pin "1") (pinfunction "1_1") (pintype "passive"))
      (node (ref "R195") (pin "1") (pinfunction "1_1") (pintype "passive"))
    )
    (net (code "32") (name "Net-(C355-Pad1)") (class "Default")
      (node (ref "C355") (pin "1") (pinfunction "1_1") (pintype "passive"))
      (node (ref "J14") (pin "1") (pinfunction "1_1") (pintype "bidirectional"))
    )
    (net (code "33") (name "Net-(IC2-CP_OUT)") (class "Default")
      (node (ref "C246") (pin "2") (pinfunction "2_2") (pintype "passive"))
      (node (ref "C282") (pin "2") (pinfunction "2_2") (pintype "passive"))
      (node (ref "C283") (pin "2") (pinfunction "2_2") (pintype "passive"))
      (node (ref "IC2") (pin "40") (pinfunction "CP_OUT_40") (pintype "output"))
      (node (ref "R195") (pin "2") (pinfunction "2_2") (pintype "passive"))
    )
    (net (code "34") (name "Net-(IC2-EXT_VCO)") (class "Default")
      (node (ref "C133") (pin "2") (pinfunction "2_2") (pintype "passive"))
      (node (ref "IC2") (pin "36") (pinfunction "EXT_VCO_36") (pintype "input"))
    )
    (net (code "35") (name "Net-(IC2-LO_OUT_N)") (class "Default")
      (node (ref "C355") (pin "2") (pinfunction "2_2") (pintype "passive"))
      (node (ref "IC2") (pin "33") (pinfunction "LO_OUT_N_33") (pintype "output"))
      (node (ref "R225") (pin "1") (pinfunction "1_1") (pintype "passive"))
    )
    (net (code "36") (name "Net-(IC2-LO_OUT_P)") (class "Default")
      (node (ref "C354") (pin "2") (pinfunction "2_2") (pintype "passive"))
      (node (ref "IC2") (pin "34") (pinfunction "LO_OUT_P_34") (pintype "output"))
      (node (ref "R224") (pin "1") (pinfunction "1_1") (pintype "passive"))
    )
    (net (code "37") (name "Net-(IC2-REFIN)") (class "Default")
      (node (ref "C43") (pin "2") (pinfunction "2_2") (pintype "passive"))
      (node (ref "IC2") (pin "43") (pinfunction "REFIN_43") (pintype "input"))
    )
    (net (code "38") (name "Net-(IC2-VTUNE)") (class "Default")
      (node (ref "C285") (pin "2") (pinfunction "2_2") (pintype "passive"))
      (node (ref "IC2") (pin "38") (pinfunction "VTUNE_38") (pintype "input"))
      (node (ref "R194") (pin "2") (pinfunction "2_2") (pintype "passive"))
    )
    (net (code "39") (name "Net-(L29-Pad2)") (class "Default")
      (node (ref "L29") (pin "2") (pinfunction "2_2") (pintype "passive"))
      (node (ref "R38") (pin "2") (pinfunction "2_2") (pintype "passive"))
    )
    (net (code "40") (name "Net-(L31-Pad2)") (class "Default")
      (node (ref "L31") (pin "2") (pinfunction "2_2") (pintype "passive"))
      (node (ref "R38") (pin "1") (pinfunction "1_1") (pintype "passive"))
    )
    (net (code "41") (name "Net-(L33-Pad2)") (class "Default")
      (node (ref "L33") (pin "2") (pinfunction "2_2") (pintype "passive"))
      (node (ref "R41") (pin "2") (pinfunction "2_2") (pintype "passive"))
    )
    (net (code "42") (name "Net-(L38-Pad2)") (class "Default")
      (node (ref "L38") (pin "2") (pinfunction "2_2") (pintype "passive"))
      (node (ref "R41") (pin "1") (pinfunction "1_1") (pintype "passive"))
    )
    (net (code "43") (name "Net-(TR6-PDOT)") (class "Default")
      (node (ref "C43") (pin "1") (pinfunction "1_1") (pintype "passive"))
      (node (ref "R193") (pin "2") (pinfunction "2_2") (pintype "passive"))
      (node (ref "TR6") (pin "6") (pinfunction "PDOT_6") (pintype "passive"))
    )
    (net (code "44") (name "P3V3A") (class "Default")
      (node (ref "L19") (pin "2") (pinfunction "2_2") (pintype "passive"))
      (node (ref "L20") (pin "2") (pinfunction "2_2") (pintype "passive"))
      (node (ref "L22") (pin "2") (pinfunction "2_2") (pintype "passive"))
      (node (ref "L24") (pin "2") (pinfunction "2_2") (pintype "passive"))
      (node (ref "L25") (pin "2") (pinfunction "2_2") (pintype "passive"))
      (node (ref "L27") (pin "1") (pinfunction "1_1") (pintype "passive"))
      (node (ref "L52") (pin "2") (pinfunction "2_2") (pintype "passive"))
    )
    (net (code "45") (name "P5V0A") (class "Default")
      (node (ref "L34") (pin "1") (pinfunction "1_1") (pintype "passive"))
      (node (ref "L35") (pin "2") (pinfunction "2_2") (pintype "passive"))
    )
    (net (code "46") (name "unconnected-(IC2-RSVD-Pad14)") (class "Default")
      (node (ref "IC2") (pin "14") (pinfunction "RSVD_14") (pintype "passive+no_connect"))
    )
  )
)
